# design.net
KiCad netlist of a schematic drawn in Altium Designer
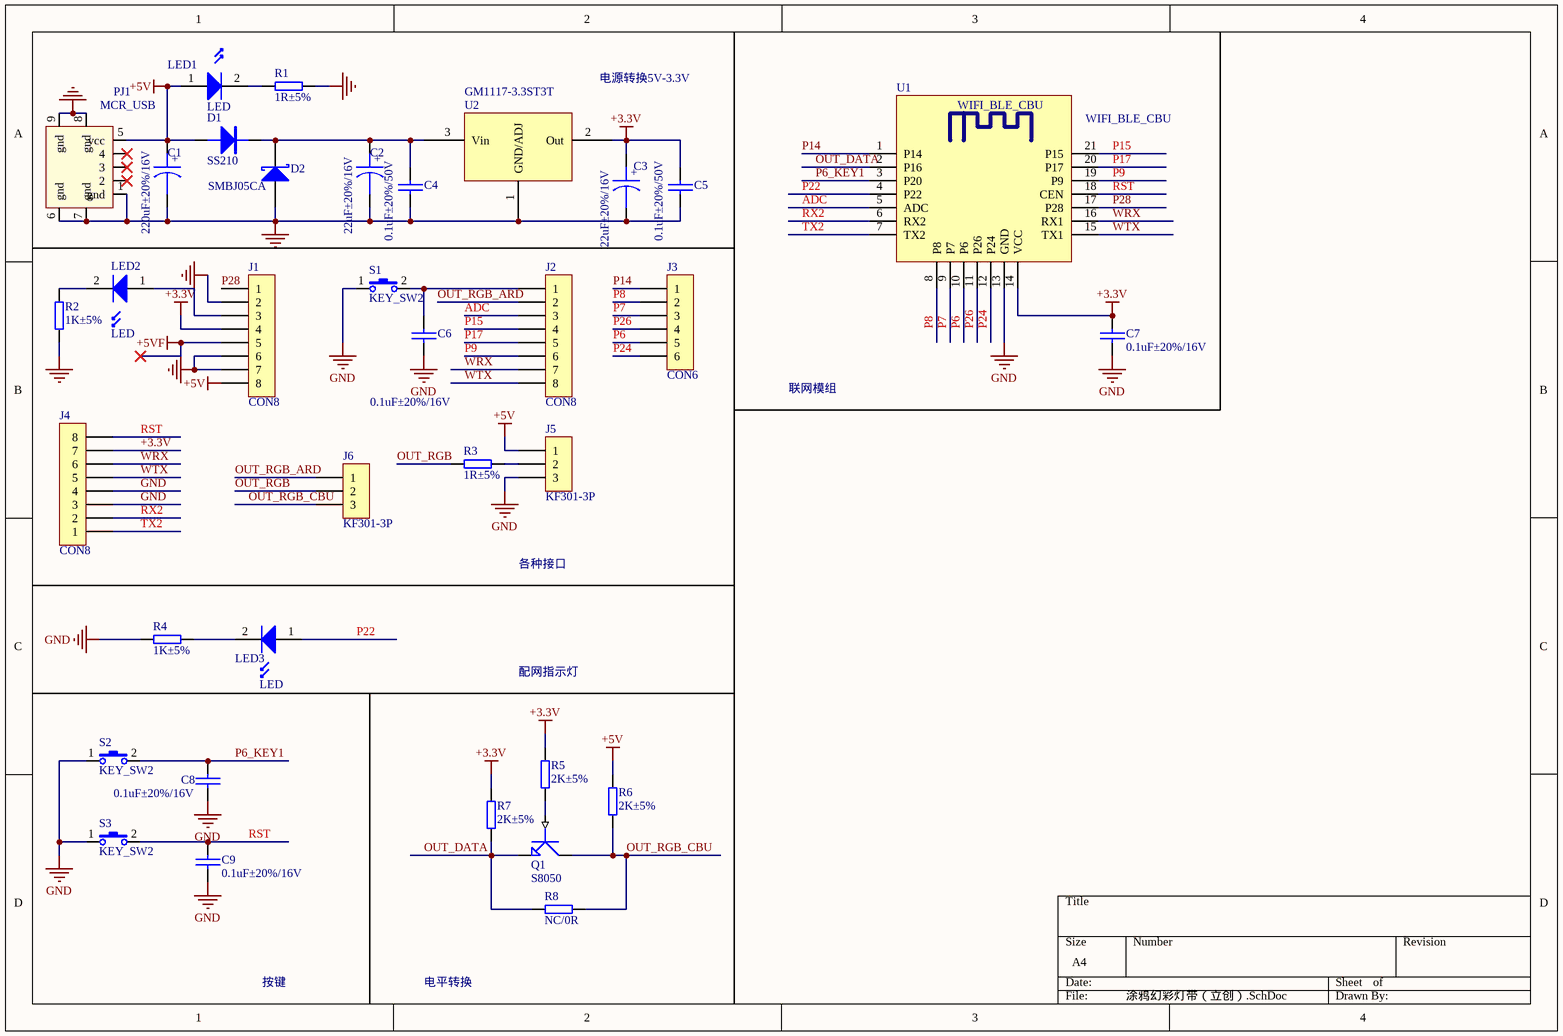
[diagram p0: 涂鸦幻彩灯带（立创）.SchDoc]

(export (version "E")
  (design (tool "Eeschema 10.0.6"))
  (components
    (comp (ref "C1")
      (value "220uF±20%/16V")
      (footprint "CD0.15")
      (description "Capacitor")
      (libsource (lib "*") (part "CAPACITOR POL"))
    )
    (comp (ref "C2")
      (value "22uF±20%/16V")
      (footprint "钽电容B3528")
      (description "Capacitor")
      (libsource (lib "*") (part "CAPACITOR POL"))
    )
    (comp (ref "C3")
      (value "22uF±20%/16V")
      (footprint "钽电容B3528")
      (description "Capacitor")
      (libsource (lib "*") (part "CAPACITOR POL"))
    )
    (comp (ref "C4")
      (value "0.1uF±20%/50V")
      (footprint "C0603")
      (description "Capacitor")
      (libsource (lib "昊华元件库sch") (part "CAP"))
    )
    (comp (ref "C5")
      (value "0.1uF±20%/50V")
      (footprint "C0603")
      (description "Capacitor")
      (libsource (lib "昊华元件库sch") (part "CAP"))
    )
    (comp (ref "C6")
      (value "0.1uF±20%/16V")
      (footprint "C0603")
      (description "Capacitor")
      (libsource (lib "昊华元件库sch") (part "CAP"))
    )
    (comp (ref "C7")
      (value "0.1uF±20%/16V")
      (footprint "C0603")
      (description "Capacitor")
      (libsource (lib "昊华元件库sch") (part "CAP"))
    )
    (comp (ref "C8")
      (value "0.1uF±20%/16V")
      (footprint "C0603")
      (description "Capacitor")
      (libsource (lib "昊华元件库sch") (part "CAP"))
    )
    (comp (ref "C9")
      (value "0.1uF±20%/16V")
      (footprint "C0603")
      (description "Capacitor")
      (libsource (lib "昊华元件库sch") (part "CAP"))
    )
    (comp (ref "D1")
      (value "SS210")
      (footprint "SMA(DO-214AC)")
      (description "Diode")
      (libsource (lib "小马元件库sch") (part "Diode1"))
    )
    (comp (ref "D2")
      (value "SMBJ05CA")
      (footprint "SMB(DO-214AA)")
      (description "Schottky Diode")
      (fields (field (name "MFR") "Toshiba"))
      (libsource (lib "Miscellaneous Devices") (part "D Schottky"))
    )
    (comp (ref "J1")
      (value "CON8")
      (footprint "HDR1X8Z")
      (description "Connector")
      (libsource (lib "小马元件库sch") (part "CON8"))
    )
    (comp (ref "J2")
      (value "CON8")
      (footprint "HDR1X8Z")
      (description "Connector")
      (libsource (lib "小马元件库sch") (part "CON8"))
    )
    (comp (ref "J3")
      (value "CON6")
      (footprint "HDR1X6Z")
      (description "Connector")
      (libsource (lib "小马元件库sch") (part "CON6"))
    )
    (comp (ref "J4")
      (value "CON8")
      (footprint "HDR1X8Z")
      (description "Connector")
      (libsource (lib "") (part "CON8_1"))
    )
    (comp (ref "J5")
      (value "KF301-3P")
      (footprint "SIP3 - 2.54")
      (description "Connector")
      (libsource (lib "小马元件库sch") (part "CON3"))
    )
    (comp (ref "J6")
      (value "KF301-3P")
      (footprint "SIP3 - 2.54")
      (description "Connector")
      (libsource (lib "小马元件库sch") (part "CON3"))
    )
    (comp (ref "LED1")
      (value "LED")
      (footprint "LED0805_1")
      (fields (field (name "PUBLISHER") "*"))
      (libsource (lib "小马元件库sch") (part "LED"))
    )
    (comp (ref "LED2")
      (value "LED")
      (footprint "LED0805_1")
      (fields (field (name "PUBLISHER") "*"))
      (libsource (lib "小马元件库sch") (part "LED"))
    )
    (comp (ref "LED3")
      (value "LED")
      (footprint "LED0805_1")
      (fields (field (name "PUBLISHER") "*"))
      (libsource (lib "小马元件库sch") (part "LED"))
    )
    (comp (ref "PJ1")
      (value "MCR_USB")
      (footprint "MICRO_USB-NEW-16.12.12")
      (fields (field (name "PUBLISHER") "*"))
      (libsource (lib "昊华元件库sch") (part "MCR_USB"))
    )
    (comp (ref "Q1")
      (value "S8050")
      (footprint "SOT-23-NPN")
      (description "NPN Transistor")
      (libsource (lib "小马元件库sch") (part "NPN"))
    )
    (comp (ref "R1") (value "1R±5%") (footprint "R0603") (libsource (lib "昊华元件库sch") (part "RES5")))
    (comp (ref "R2") (value "1K±5%") (footprint "R0603") (libsource (lib "昊华元件库sch") (part "RES5")))
    (comp (ref "R3") (value "1R±5%") (footprint "R0603") (libsource (lib "昊华元件库sch") (part "RES5")))
    (comp (ref "R4") (value "1K±5%") (footprint "R0603") (libsource (lib "昊华元件库sch") (part "RES5")))
    (comp (ref "R5") (value "2K±5%") (footprint "R0603") (libsource (lib "昊华元件库sch") (part "RES5")))
    (comp (ref "R6") (value "2K±5%") (footprint "R0603") (libsource (lib "昊华元件库sch") (part "RES5")))
    (comp (ref "R7") (value "2K±5%") (footprint "R0603") (libsource (lib "昊华元件库sch") (part "RES5")))
    (comp (ref "R8") (value "NC/0R") (footprint "R0603") (libsource (lib "昊华元件库sch") (part "RES5")))
    (comp (ref "S1") (value "KEY_SW2") (footprint "KEY4-SMD") (libsource (lib "小马元件库sch") (part "KEY_SW2")))
    (comp (ref "S2") (value "KEY_SW2") (footprint "KEY4-SMD") (libsource (lib "小马元件库sch") (part "KEY_SW2")))
    (comp (ref "S3") (value "KEY_SW2") (footprint "KEY4-SMD") (libsource (lib "小马元件库sch") (part "KEY_SW2")))
    (comp (ref "U1")
      (value "WIFI_BLE_CBU")
      (footprint "WIFI_BLE_CBU")
      (description "Module")
      (libsource (lib "TYModeSchlib V03") (part "WIFI_BLE_CBU"))
    )
    (comp (ref "U2") (value "GM1117-3.3ST3T") (footprint "SOT-223") (libsource (lib "mylib") (part "GM1117")))
  )
  (nets
    (net (code "1") (name "+3.3V") (class "Default")
      (node (ref "C3") (pin "1") (pinfunction "1_1") (pintype "passive"))
      (node (ref "C5") (pin "1") (pinfunction "1_1") (pintype "passive"))
      (node (ref "C7") (pin "2") (pinfunction "2_2") (pintype "passive"))
      (node (ref "J1") (pin "4") (pinfunction "4_4") (pintype "passive"))
      (node (ref "J4") (pin "7") (pinfunction "7_7") (pintype "passive"))
      (node (ref "R5") (pin "1") (pinfunction "1_1") (pintype "passive"))
      (node (ref "R7") (pin "1") (pinfunction "1_1") (pintype "passive"))
      (node (ref "U1") (pin "14") (pinfunction "VCC_14") (pintype "passive"))
      (node (ref "U2") (pin "2") (pinfunction "Out_2") (pintype "passive"))
    )
    (net (code "2") (name "+5V") (class "Default")
      (node (ref "C1") (pin "1") (pinfunction "1_1") (pintype "passive"))
      (node (ref "D1") (pin "1") (pinfunction "1_1") (pintype "passive"))
      (node (ref "J1") (pin "8") (pinfunction "8_8") (pintype "passive"))
      (node (ref "J5") (pin "1") (pinfunction "1_1") (pintype "passive"))
      (node (ref "LED1") (pin "1") (pinfunction "1_1") (pintype "passive"))
      (node (ref "PJ1") (pin "5") (pinfunction "vcc_5") (pintype "passive"))
      (node (ref "R6") (pin "1") (pinfunction "1_1") (pintype "passive"))
    )
    (net (code "3") (name "+5VF") (class "Default")
      (node (ref "J1") (pin "5") (pinfunction "5_5") (pintype "passive"))
    )
    (net (code "4") (name "/ADC") (class "Default")
      (node (ref "J2") (pin "3") (pinfunction "3_3") (pintype "passive"))
      (node (ref "U1") (pin "5") (pinfunction "ADC_5") (pintype "passive"))
    )
    (net (code "5") (name "/OUT_DATA") (class "Default")
      (node (ref "Q1") (pin "1") (pinfunction "E_1") (pintype "passive"))
      (node (ref "R7") (pin "2") (pinfunction "2_2") (pintype "passive"))
      (node (ref "R8") (pin "1") (pinfunction "1_1") (pintype "passive"))
      (node (ref "U1") (pin "2") (pinfunction "P16_2") (pintype "passive"))
    )
    (net (code "6") (name "/OUT_RGB") (class "Default")
      (node (ref "J6") (pin "2") (pinfunction "2_2") (pintype "passive"))
      (node (ref "R3") (pin "1") (pinfunction "1_1") (pintype "passive"))
    )
    (net (code "7") (name "/OUT_RGB_ARD") (class "Default")
      (node (ref "J2") (pin "2") (pinfunction "2_2") (pintype "passive"))
      (node (ref "J6") (pin "1") (pinfunction "1_1") (pintype "passive"))
    )
    (net (code "8") (name "/OUT_RGB_CBU") (class "Default")
      (node (ref "J6") (pin "3") (pinfunction "3_3") (pintype "passive"))
      (node (ref "Q1") (pin "3") (pinfunction "C_3") (pintype "passive"))
      (node (ref "R6") (pin "2") (pinfunction "2_2") (pintype "passive"))
      (node (ref "R8") (pin "2") (pinfunction "2_2") (pintype "passive"))
    )
    (net (code "9") (name "/P6") (class "Default")
      (node (ref "J3") (pin "5") (pinfunction "5_5") (pintype "passive"))
      (node (ref "U1") (pin "10") (pinfunction "P6_10") (pintype "passive"))
    )
    (net (code "10") (name "/P6_KEY1") (class "Default")
      (node (ref "C8") (pin "2") (pinfunction "2_2") (pintype "passive"))
      (node (ref "S2") (pin "2") (pinfunction "2_2") (pintype "passive"))
      (node (ref "U1") (pin "3") (pinfunction "P20_3") (pintype "passive"))
    )
    (net (code "11") (name "/P7") (class "Default")
      (node (ref "J3") (pin "3") (pinfunction "3_3") (pintype "passive"))
      (node (ref "U1") (pin "9") (pinfunction "P7_9") (pintype "passive"))
    )
    (net (code "12") (name "/P8") (class "Default")
      (node (ref "J3") (pin "2") (pinfunction "2_2") (pintype "passive"))
      (node (ref "U1") (pin "8") (pinfunction "P8_8") (pintype "passive"))
    )
    (net (code "13") (name "/P9") (class "Default")
      (node (ref "J2") (pin "6") (pinfunction "6_6") (pintype "passive"))
      (node (ref "U1") (pin "19") (pinfunction "P9_19") (pintype "passive"))
    )
    (net (code "14") (name "/P14") (class "Default")
      (node (ref "J3") (pin "1") (pinfunction "1_1") (pintype "passive"))
      (node (ref "U1") (pin "1") (pinfunction "P14_1") (pintype "passive"))
    )
    (net (code "15") (name "/P15") (class "Default")
      (node (ref "J2") (pin "4") (pinfunction "4_4") (pintype "passive"))
      (node (ref "U1") (pin "21") (pinfunction "P15_21") (pintype "passive"))
    )
    (net (code "16") (name "/P17") (class "Default")
      (node (ref "J2") (pin "5") (pinfunction "5_5") (pintype "passive"))
      (node (ref "U1") (pin "20") (pinfunction "P17_20") (pintype "passive"))
    )
    (net (code "17") (name "/P22") (class "Default")
      (node (ref "LED3") (pin "1") (pinfunction "1_1") (pintype "passive"))
      (node (ref "U1") (pin "4") (pinfunction "P22_4") (pintype "passive"))
    )
    (net (code "18") (name "/P24") (class "Default")
      (node (ref "J3") (pin "6") (pinfunction "6_6") (pintype "passive"))
      (node (ref "U1") (pin "12") (pinfunction "P24_12") (pintype "passive"))
    )
    (net (code "19") (name "/P26") (class "Default")
      (node (ref "J3") (pin "4") (pinfunction "4_4") (pintype "passive"))
      (node (ref "U1") (pin "11") (pinfunction "P26_11") (pintype "passive"))
    )
    (net (code "20") (name "/P28") (class "Default")
      (node (ref "J1") (pin "1") (pinfunction "1_1") (pintype "passive"))
      (node (ref "U1") (pin "17") (pinfunction "P28_17") (pintype "passive"))
    )
    (net (code "21") (name "/RST") (class "Default")
      (node (ref "C9") (pin "1") (pinfunction "1_1") (pintype "passive"))
      (node (ref "J4") (pin "8") (pinfunction "8_8") (pintype "passive"))
      (node (ref "S3") (pin "2") (pinfunction "2_2") (pintype "passive"))
      (node (ref "U1") (pin "18") (pinfunction "CEN_18") (pintype "passive"))
    )
    (net (code "22") (name "/RX2") (class "Default")
      (node (ref "J4") (pin "2") (pinfunction "2_2") (pintype "passive"))
      (node (ref "U1") (pin "6") (pinfunction "RX2_6") (pintype "passive"))
    )
    (net (code "23") (name "/TX2") (class "Default")
      (node (ref "J4") (pin "1") (pinfunction "1_1") (pintype "passive"))
      (node (ref "U1") (pin "7") (pinfunction "TX2_7") (pintype "passive"))
    )
    (net (code "24") (name "/WRX") (class "Default")
      (node (ref "J2") (pin "7") (pinfunction "7_7") (pintype "passive"))
      (node (ref "J4") (pin "6") (pinfunction "6_6") (pintype "passive"))
      (node (ref "U1") (pin "16") (pinfunction "RX1_16") (pintype "passive"))
    )
    (net (code "25") (name "/WTX") (class "Default")
      (node (ref "J2") (pin "8") (pinfunction "8_8") (pintype "passive"))
      (node (ref "J4") (pin "5") (pinfunction "5_5") (pintype "passive"))
      (node (ref "U1") (pin "15") (pinfunction "TX1_15") (pintype "passive"))
    )
    (net (code "26") (name "GND") (class "Default")
      (node (ref "C1") (pin "2") (pinfunction "2_2") (pintype "passive"))
      (node (ref "C2") (pin "2") (pinfunction "2_2") (pintype "passive"))
      (node (ref "C3") (pin "2") (pinfunction "2_2") (pintype "passive"))
      (node (ref "C4") (pin "2") (pinfunction "2_2") (pintype "passive"))
      (node (ref "C5") (pin "2") (pinfunction "2_2") (pintype "passive"))
      (node (ref "C6") (pin "1") (pinfunction "1_1") (pintype "passive"))
      (node (ref "C7") (pin "1") (pinfunction "1_1") (pintype "passive"))
      (node (ref "C8") (pin "1") (pinfunction "1_1") (pintype "passive"))
      (node (ref "C9") (pin "2") (pinfunction "2_2") (pintype "passive"))
      (node (ref "D2") (pin "1") (pinfunction "A_1") (pintype "passive"))
      (node (ref "J1") (pin "2") (pinfunction "2_2") (pintype "passive"))
      (node (ref "J1") (pin "6") (pinfunction "6_6") (pintype "passive"))
      (node (ref "J1") (pin "7") (pinfunction "7_7") (pintype "passive"))
      (node (ref "J4") (pin "3") (pinfunction "3_3") (pintype "passive"))
      (node (ref "J4") (pin "4") (pinfunction "4_4") (pintype "passive"))
      (node (ref "J5") (pin "3") (pinfunction "3_3") (pintype "passive"))
      (node (ref "PJ1") (pin "1") (pinfunction "gnd_1") (pintype "passive"))
      (node (ref "PJ1") (pin "6") (pinfunction "gnd_6") (pintype "passive"))
      (node (ref "PJ1") (pin "7") (pinfunction "gnd_7") (pintype "passive"))
      (node (ref "PJ1") (pin "8") (pinfunction "gnd_8") (pintype "passive"))
      (node (ref "PJ1") (pin "9") (pinfunction "gnd_9") (pintype "passive"))
      (node (ref "R1") (pin "2") (pinfunction "2_2") (pintype "passive"))
      (node (ref "R2") (pin "1") (pinfunction "1_1") (pintype "passive"))
      (node (ref "R4") (pin "2") (pinfunction "2_2") (pintype "passive"))
      (node (ref "S1") (pin "1") (pinfunction "1_1") (pintype "passive"))
      (node (ref "S2") (pin "1") (pinfunction "1_1") (pintype "passive"))
      (node (ref "S3") (pin "1") (pinfunction "1_1") (pintype "passive"))
      (node (ref "U1") (pin "13") (pinfunction "GND_13") (pintype "passive"))
      (node (ref "U2") (pin "1") (pinfunction "GND/ADJ_1") (pintype "passive"))
    )
    (net (code "27") (name "Net-(C6-Pad2)") (class "Default")
      (node (ref "C6") (pin "2") (pinfunction "2_2") (pintype "passive"))
      (node (ref "J2") (pin "1") (pinfunction "1_1") (pintype "passive"))
      (node (ref "S1") (pin "2") (pinfunction "2_2") (pintype "passive"))
    )
    (net (code "28") (name "Net-(D2-K)") (class "Default")
      (node (ref "C2") (pin "1") (pinfunction "1_1") (pintype "passive"))
      (node (ref "C4") (pin "1") (pinfunction "1_1") (pintype "passive"))
      (node (ref "D1") (pin "2") (pinfunction "2_2") (pintype "passive"))
      (node (ref "D2") (pin "2") (pinfunction "K_2") (pintype "passive"))
      (node (ref "U2") (pin "3") (pinfunction "Vin_3") (pintype "passive"))
    )
    (net (code "29") (name "Net-(J1-Pad3)") (class "Default")
      (node (ref "J1") (pin "3") (pinfunction "3_3") (pintype "passive"))
      (node (ref "LED2") (pin "1") (pinfunction "1_1") (pintype "passive"))
    )
    (net (code "30") (name "Net-(J5-Pad2)") (class "Default")
      (node (ref "J5") (pin "2") (pinfunction "2_2") (pintype "passive"))
      (node (ref "R3") (pin "2") (pinfunction "2_2") (pintype "passive"))
    )
    (net (code "31") (name "Net-(LED1-Pad2)") (class "Default")
      (node (ref "LED1") (pin "2") (pinfunction "2_2") (pintype "passive"))
      (node (ref "R1") (pin "1") (pinfunction "1_1") (pintype "passive"))
    )
    (net (code "32") (name "Net-(LED2-Pad2)") (class "Default")
      (node (ref "LED2") (pin "2") (pinfunction "2_2") (pintype "passive"))
      (node (ref "R2") (pin "2") (pinfunction "2_2") (pintype "passive"))
    )
    (net (code "33") (name "Net-(LED3-Pad2)") (class "Default")
      (node (ref "LED3") (pin "2") (pinfunction "2_2") (pintype "passive"))
      (node (ref "R4") (pin "1") (pinfunction "1_1") (pintype "passive"))
    )
    (net (code "34") (name "Net-(Q1-B)") (class "Default")
      (node (ref "Q1") (pin "2") (pinfunction "B_2") (pintype "input"))
      (node (ref "R5") (pin "2") (pinfunction "2_2") (pintype "passive"))
    )
    (net (code "35") (name "unconnected-(PJ1-Pad2)") (class "Default")
      (node (ref "PJ1") (pin "2") (pinfunction "2_2") (pintype "passive+no_connect"))
    )
    (net (code "36") (name "unconnected-(PJ1-Pad3)") (class "Default")
      (node (ref "PJ1") (pin "3") (pinfunction "3_3") (pintype "passive+no_connect"))
    )
    (net (code "37") (name "unconnected-(PJ1-Pad4)") (class "Default")
      (node (ref "PJ1") (pin "4") (pinfunction "4_4") (pintype "passive+no_connect"))
    )
  )
)
